# STM32_microcontroller_power.net
KiCad netlist of a schematic drawn in Altium Designer
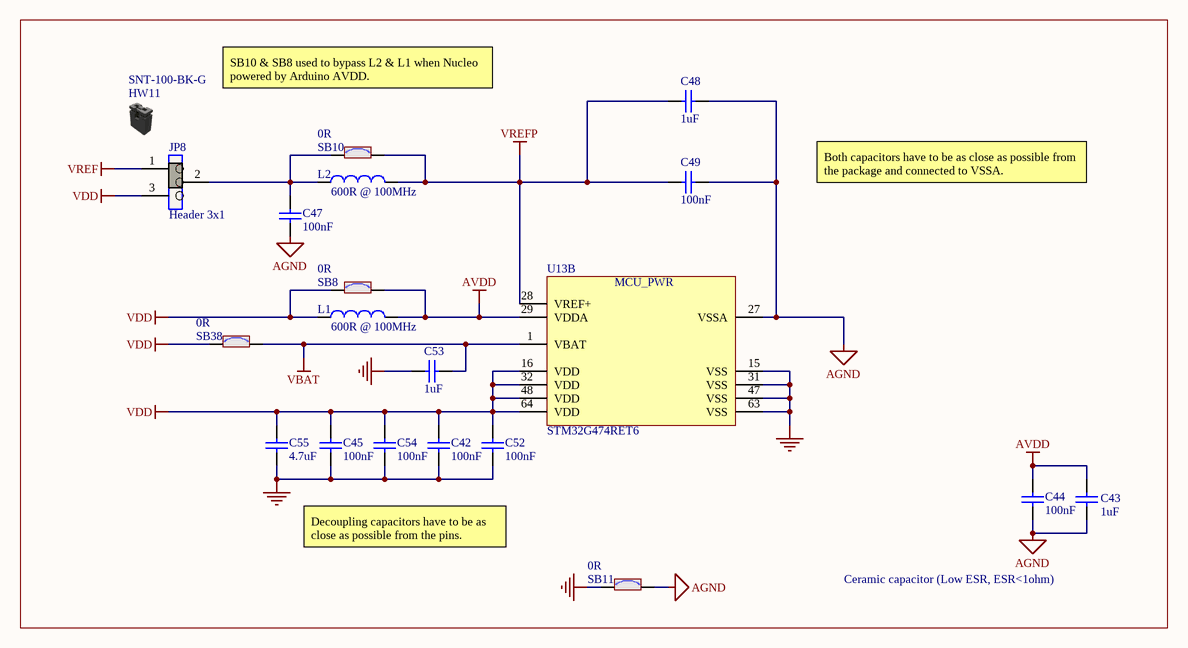
[diagram p0: STM32_microcontroller_power.SchDoc]

(export (version "E")
  (design (tool "Eeschema 10.0.6"))
  (components
    (comp (ref "C42")
      (value "100nF")
      (footprint "C0402")
      (description "Capacitor, MLCC, 100nF, 16V, X7R, +/-10%, 0402, T=0.5mm")
      (fields
        (field (name "INTERNAL_PART_NUMBER") "MCD-00006")
        (field (name "MANUFACTURER_PART_NUMBER") "CC0402KRX7R7BB104")
      )
      (libsource (lib "MCD_PARTS_database") (part "Capacitor"))
    )
    (comp (ref "C43")
      (value "1uF")
      (footprint "C0603")
      (description "Capacitor, MLCC, 1uF, 16V, X5R, 10%, 0603, T=0,8mm")
      (fields
        (field (name "INTERNAL_PART_NUMBER") "MCD-00010")
        (field (name "MANUFACTURER_PART_NUMBER") "CC0603KRX5R7BB105")
        (field (name "PROVIDED_BY") "Subcon")
      )
      (libsource (lib "MCD_PARTS_database") (part "Capacitor"))
    )
    (comp (ref "C44")
      (value "100nF")
      (footprint "C0402")
      (description "Capacitor, MLCC, 100nF, 16V, X7R, +/-10%, 0402, T=0.5mm")
      (fields
        (field (name "INTERNAL_PART_NUMBER") "MCD-00006")
        (field (name "MANUFACTURER_PART_NUMBER") "CC0402KRX7R7BB104")
      )
      (libsource (lib "MCD_PARTS_database") (part "Capacitor"))
    )
    (comp (ref "C45")
      (value "100nF")
      (footprint "C0402")
      (description "Capacitor, MLCC, 100nF, 16V, X7R, +/-10%, 0402, T=0.5mm")
      (fields
        (field (name "INTERNAL_PART_NUMBER") "MCD-00006")
        (field (name "MANUFACTURER_PART_NUMBER") "CC0402KRX7R7BB104")
      )
      (libsource (lib "MCD_PARTS_database") (part "Capacitor"))
    )
    (comp (ref "C47")
      (value "100nF")
      (footprint "C0402")
      (description "Capacitor, MLCC, 100nF, 16V, X7R, +/-10%, 0402, T=0.5mm")
      (fields
        (field (name "INTERNAL_PART_NUMBER") "MCD-00006")
        (field (name "MANUFACTURER_PART_NUMBER") "CC0402KRX7R7BB104")
      )
      (libsource (lib "MCD_PARTS_database") (part "Capacitor"))
    )
    (comp (ref "C48")
      (value "1uF")
      (footprint "C0603")
      (description "Capacitor, MLCC, 1uF, 16V, X5R, 10%, 0603, T=0,8mm")
      (fields
        (field (name "INTERNAL_PART_NUMBER") "MCD-00010")
        (field (name "MANUFACTURER_PART_NUMBER") "CC0603KRX5R7BB105")
        (field (name "PROVIDED_BY") "Subcon")
      )
      (libsource (lib "MCD_PARTS_database") (part "Capacitor"))
    )
    (comp (ref "C49")
      (value "100nF")
      (footprint "C0402")
      (description "Capacitor, MLCC, 100nF, 16V, X7R, +/-10%, 0402, T=0.5mm")
      (fields
        (field (name "INTERNAL_PART_NUMBER") "MCD-00006")
        (field (name "MANUFACTURER_PART_NUMBER") "CC0402KRX7R7BB104")
      )
      (libsource (lib "MCD_PARTS_database") (part "Capacitor"))
    )
    (comp (ref "C52")
      (value "100nF")
      (footprint "C0402")
      (description "Capacitor, MLCC, 100nF, 16V, X7R, +/-10%, 0402, T=0.5mm")
      (fields
        (field (name "INTERNAL_PART_NUMBER") "MCD-00006")
        (field (name "MANUFACTURER_PART_NUMBER") "CC0402KRX7R7BB104")
      )
      (libsource (lib "MCD_PARTS_database") (part "Capacitor"))
    )
    (comp (ref "C53")
      (value "1uF")
      (footprint "C0603")
      (description "Capacitor, MLCC, 1uF, 16V, X5R, 10%, 0603, T=0,8mm")
      (fields
        (field (name "INTERNAL_PART_NUMBER") "MCD-00010")
        (field (name "MANUFACTURER_PART_NUMBER") "CC0603KRX5R7BB105")
        (field (name "PROVIDED_BY") "Subcon")
      )
      (libsource (lib "MCD_PARTS_database") (part "Capacitor"))
    )
    (comp (ref "C54")
      (value "100nF")
      (footprint "C0402")
      (description "Capacitor, MLCC, 100nF, 16V, X7R, +/-10%, 0402, T=0.5mm")
      (fields
        (field (name "INTERNAL_PART_NUMBER") "MCD-00006")
        (field (name "MANUFACTURER_PART_NUMBER") "CC0402KRX7R7BB104")
      )
      (libsource (lib "MCD_PARTS_database") (part "Capacitor"))
    )
    (comp (ref "C55")
      (value "4.7uF")
      (footprint "C0603")
      (description "Capacitor, MLCC, 4.7uF, 16V, X5R, 10%, 0603, T=0.8mm")
      (fields
        (field (name "INTERNAL_PART_NUMBER") "MCD-00009")
        (field (name "MANUFACTURER_PART_NUMBER") "CC0603KRX5R7BB475")
        (field (name "PROVIDED_BY") "subcon")
      )
      (libsource (lib "MCD_PARTS_database") (part "Capacitor"))
    )
    (comp (ref "HW11")
      (value "SNT-100-BK-G")
      (description "SHUNT 2.54mm BLACK")
      (fields
        (field (name "INTERNAL_PART_NUMBER") "MCD-00043")
        (field (name "MANUFACTURER") "SAMTEC")
        (field (name "PROVIDED_BY") "Subcon")
      )
      (libsource (lib "MCD_PARTS_database") (part "Shunt Black 2.54mm"))
    )
    (comp (ref "JP8")
      (value "Header 3x1")
      (footprint "CON_SAMTEC_TSW-103-07-F-S")
      (description "Header, 3x1, 2,54mm, VR, TH, Height 5.84mm/2.54mm - Shunt Fitted 1-2 by default")
      (fields
        (field (name "INTERNAL_PART_NUMBER") "MCD-00684")
        (field (name "MANUFACTURER_PART_NUMBER") "TSW-103-07-F-S")
        (field (name "PROVIDED_BY") "SUBCO")
      )
      (libsource (lib "MCD_PARTS_database") (part "Jumper_Header 3x1 Fitted 1-2"))
    )
    (comp (ref "L1")
      (value "600R @ 100MHz")
      (footprint "L0603")
      (description "SMD Chip ferrite bead, 600R@100MHz +/-25%, 350mA, 500mohm DC, 0603, T=0.8mm")
      (fields
        (field (name "INTERNAL_PART_NUMBER") "MCD-00047")
        (field (name "MANUFACTURER_PART_NUMBER") "FCM1608KF-601T03")
        (field (name "PROVIDED_BY") "SUBCO")
      )
      (libsource (lib "MCD_PARTS_database") (part "BEAD"))
    )
    (comp (ref "L2")
      (value "600R @ 100MHz")
      (footprint "L0603")
      (description "SMD Chip ferrite bead, 600R@100MHz +/-25%, 350mA, 500mohm DC, 0603, T=0.8mm")
      (fields
        (field (name "INTERNAL_PART_NUMBER") "MCD-00047")
        (field (name "MANUFACTURER_PART_NUMBER") "FCM1608KF-601T03")
        (field (name "PROVIDED_BY") "SUBCO")
      )
      (libsource (lib "MCD_PARTS_database") (part "BEAD"))
    )
    (comp (ref "SB8")
      (value "0R")
      (footprint "SOLDER-BRIDGE_R0603-0R")
      (description "Solder Bridge ON")
      (fields
        (field (name "INTERNAL_PART_NUMBER") "MCD-00071")
        (field (name "MANUFACTURER_PART_NUMBER") "RC0603JR-070RL")
        (field (name "PROVIDED_BY") "SUBCO")
      )
      (libsource (lib "MCD_PARTS_database") (part "SB_ON"))
    )
    (comp (ref "SB10")
      (value "0R")
      (footprint "SOLDER-BRIDGE_R0603-0R")
      (description "Solder Bridge ON")
      (fields
        (field (name "INTERNAL_PART_NUMBER") "MCD-00071")
        (field (name "MANUFACTURER_PART_NUMBER") "RC0603JR-070RL")
        (field (name "PROVIDED_BY") "SUBCO")
      )
      (libsource (lib "MCD_PARTS_database") (part "SB_ON"))
    )
    (comp (ref "SB11")
      (value "0R")
      (footprint "SOLDER-BRIDGE_R0603-0R")
      (description "Solder Bridge ON")
      (fields
        (field (name "INTERNAL_PART_NUMBER") "MCD-00071")
        (field (name "MANUFACTURER_PART_NUMBER") "RC0603JR-070RL")
        (field (name "PROVIDED_BY") "SUBCO")
      )
      (libsource (lib "MCD_PARTS_database") (part "SB_ON"))
    )
    (comp (ref "SB38")
      (value "0R")
      (footprint "SOLDER-BRIDGE_R0603-0R")
      (description "Solder Bridge ON")
      (fields
        (field (name "INTERNAL_PART_NUMBER") "MCD-00071")
        (field (name "MANUFACTURER_PART_NUMBER") "RC0603JR-070RL")
        (field (name "PROVIDED_BY") "SUBCO")
      )
      (libsource (lib "MCD_PARTS_database") (part "SB_ON"))
    )
    (comp (ref "U13")
      (value "STM32G474RET6")
      (footprint "ICC_LQFP64_10X10_P050_SOCKET_YAMAICHI_IC149-064-069-B5_NM")
      (description "STM32G474, LQFP64 package,  3D IC footprint with 2D socket footprint.")
      (fields
        (field (name "INTERNAL_PART_NUMBER") "MCD-01243")
        (field (name "MANUFACTURER") "STMICROELECTRONICS")
        (field (name "PROVIDED_BY") "SUBCO with ST control")
      )
      (libsource (lib "MCD_PARTS_database") (part "STM32G4xx_LQFP64"))
    )
  )
  (nets
    (net (code "1") (name "AGND") (class "Default")
      (node (ref "C43") (pin "1") (pinfunction "1_1") (pintype "passive"))
      (node (ref "C44") (pin "1") (pinfunction "1_1") (pintype "passive"))
      (node (ref "C47") (pin "1") (pinfunction "1_1") (pintype "passive"))
      (node (ref "C48") (pin "2") (pinfunction "2_2") (pintype "passive"))
      (node (ref "C49") (pin "2") (pinfunction "2_2") (pintype "passive"))
      (node (ref "SB11") (pin "2") (pinfunction "2_2") (pintype "passive"))
      (node (ref "U13") (pin "27") (pinfunction "VSSA_27") (pintype "passive"))
    )
    (net (code "2") (name "AVDD") (class "Default")
      (node (ref "C43") (pin "2") (pinfunction "2_2") (pintype "passive"))
      (node (ref "C44") (pin "2") (pinfunction "2_2") (pintype "passive"))
      (node (ref "L1") (pin "2") (pinfunction "2_2") (pintype "passive"))
      (node (ref "SB8") (pin "2") (pinfunction "2_2") (pintype "passive"))
      (node (ref "U13") (pin "29") (pinfunction "VDDA_29") (pintype "passive"))
    )
    (net (code "3") (name "GND") (class "Default")
      (node (ref "C42") (pin "1") (pinfunction "1_1") (pintype "passive"))
      (node (ref "C45") (pin "1") (pinfunction "1_1") (pintype "passive"))
      (node (ref "C52") (pin "1") (pinfunction "1_1") (pintype "passive"))
      (node (ref "C53") (pin "1") (pinfunction "1_1") (pintype "passive"))
      (node (ref "C54") (pin "1") (pinfunction "1_1") (pintype "passive"))
      (node (ref "C55") (pin "1") (pinfunction "1_1") (pintype "passive"))
      (node (ref "SB11") (pin "1") (pinfunction "1_1") (pintype "passive"))
      (node (ref "U13") (pin "15") (pinfunction "VSS_15") (pintype "passive"))
      (node (ref "U13") (pin "31") (pinfunction "VSS_31") (pintype "passive"))
      (node (ref "U13") (pin "47") (pinfunction "VSS_47") (pintype "passive"))
      (node (ref "U13") (pin "63") (pinfunction "VSS_63") (pintype "passive"))
    )
    (net (code "4") (name "Net-(C47-Pad2)") (class "Default")
      (node (ref "C47") (pin "2") (pinfunction "2_2") (pintype "passive"))
      (node (ref "JP8") (pin "2") (pinfunction "2_2") (pintype "passive"))
      (node (ref "L2") (pin "1") (pinfunction "1_1") (pintype "passive"))
      (node (ref "SB10") (pin "1") (pinfunction "1_1") (pintype "passive"))
    )
    (net (code "5") (name "VBAT") (class "Default")
      (node (ref "C53") (pin "2") (pinfunction "2_2") (pintype "passive"))
      (node (ref "SB38") (pin "2") (pinfunction "2_2") (pintype "passive"))
      (node (ref "U13") (pin "1") (pinfunction "VBAT_1") (pintype "passive"))
    )
    (net (code "6") (name "VDD") (class "Default")
      (node (ref "C42") (pin "2") (pinfunction "2_2") (pintype "passive"))
      (node (ref "C45") (pin "2") (pinfunction "2_2") (pintype "passive"))
      (node (ref "C52") (pin "2") (pinfunction "2_2") (pintype "passive"))
      (node (ref "C54") (pin "2") (pinfunction "2_2") (pintype "passive"))
      (node (ref "C55") (pin "2") (pinfunction "2_2") (pintype "passive"))
      (node (ref "JP8") (pin "3") (pinfunction "3_3") (pintype "passive"))
      (node (ref "L1") (pin "1") (pinfunction "1_1") (pintype "passive"))
      (node (ref "SB38") (pin "1") (pinfunction "1_1") (pintype "passive"))
      (node (ref "SB8") (pin "1") (pinfunction "1_1") (pintype "passive"))
      (node (ref "U13") (pin "16") (pinfunction "VDD_16") (pintype "passive"))
      (node (ref "U13") (pin "32") (pinfunction "VDD_32") (pintype "passive"))
      (node (ref "U13") (pin "48") (pinfunction "VDD_48") (pintype "passive"))
      (node (ref "U13") (pin "64") (pinfunction "VDD_64") (pintype "passive"))
    )
    (net (code "7") (name "VREF") (class "Default")
      (node (ref "JP8") (pin "1") (pinfunction "1_1") (pintype "passive"))
    )
    (net (code "8") (name "VREFP") (class "Default")
      (node (ref "C48") (pin "1") (pinfunction "1_1") (pintype "passive"))
      (node (ref "C49") (pin "1") (pinfunction "1_1") (pintype "passive"))
      (node (ref "L2") (pin "2") (pinfunction "2_2") (pintype "passive"))
      (node (ref "SB10") (pin "2") (pinfunction "2_2") (pintype "passive"))
      (node (ref "U13") (pin "28") (pinfunction "VREF+_28") (pintype "passive"))
    )
  )
)
